# Board_A_Schematic.net
KiCad netlist of a schematic drawn in EasyEDA
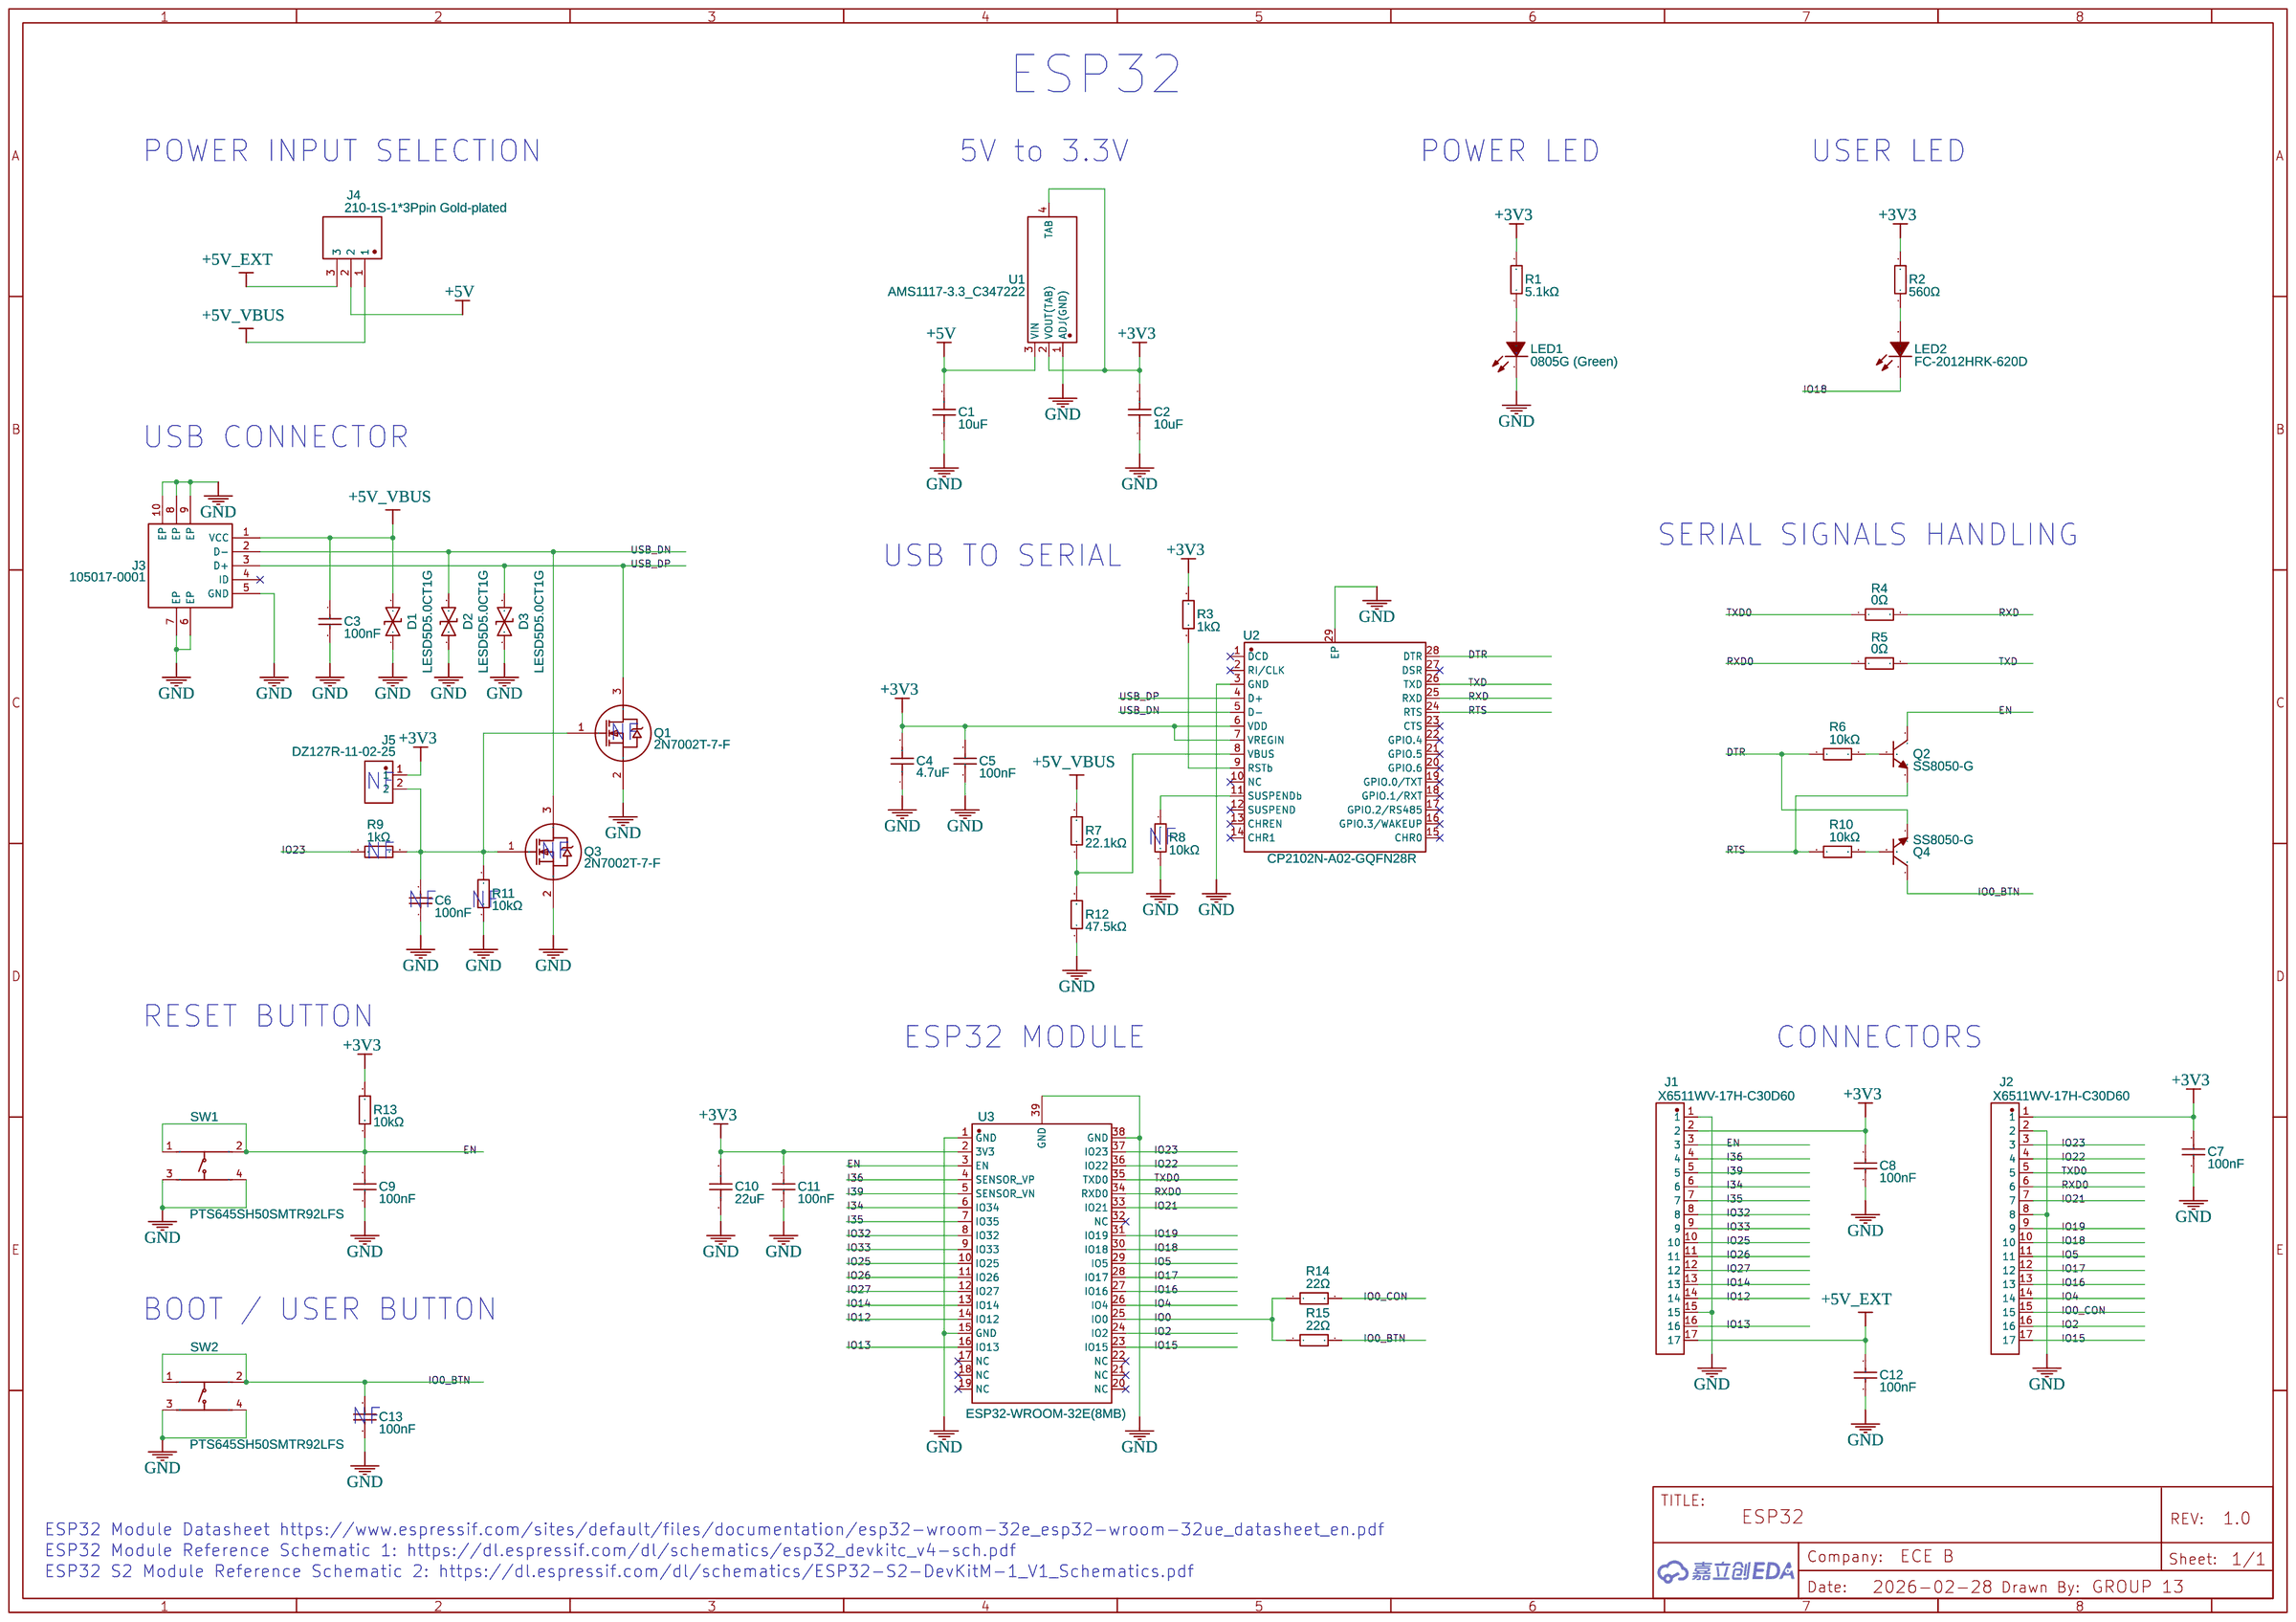
[diagram p0: schematic sheet]

(export (version "E")
  (design (tool "Eeschema 10.0.6"))
  (components
    (comp (ref "C1")
      (value "10uF")
      (fields
        (field (name "Manufacturer Part") "CL05A106MP5NUNC")
        (field (name "Manufacturer") "Samsung Electro-Mechanics")
      )
      (libsource (lib "") (part "CL05A106MP5NUNC_C315248"))
    )
    (comp (ref "C2")
      (value "10uF")
      (fields
        (field (name "Manufacturer Part") "CL05A106MP5NUNC")
        (field (name "Manufacturer") "Samsung Electro-Mechanics")
      )
      (libsource (lib "") (part "CL05A106MP5NUNC_C315248"))
    )
    (comp (ref "C3")
      (value "100nF")
      (fields (field (name "Manufacturer Part") "CL05B104KO5NNNC") (field (name "Manufacturer") "SAMSUNG"))
      (libsource (lib "") (part "CL05B104KO5NNNC"))
    )
    (comp (ref "C4")
      (value "4.7uF")
      (fields
        (field (name "Manufacturer Part") "CL05A475KP5NRNC")
        (field (name "Manufacturer") "Samsung Electro-Mechanics")
      )
      (libsource (lib "") (part "CL05A475KP5NRNC"))
    )
    (comp (ref "C5")
      (value "100nF")
      (fields (field (name "Manufacturer Part") "CL05B104KO5NNNC") (field (name "Manufacturer") "SAMSUNG"))
      (libsource (lib "") (part "CL05B104KO5NNNC"))
    )
    (comp (ref "C6")
      (value "100nF")
      (fields (field (name "Manufacturer Part") "CL05B104KO5NNNC") (field (name "Manufacturer") "SAMSUNG"))
      (libsource (lib "") (part "CL05B104KO5NNNC"))
    )
    (comp (ref "C7")
      (value "100nF")
      (fields (field (name "Manufacturer Part") "CL05B104KO5NNNC") (field (name "Manufacturer") "SAMSUNG"))
      (libsource (lib "") (part "CL05B104KO5NNNC"))
    )
    (comp (ref "C8")
      (value "100nF")
      (fields (field (name "Manufacturer Part") "CL05B104KO5NNNC") (field (name "Manufacturer") "SAMSUNG"))
      (libsource (lib "") (part "CL05B104KO5NNNC"))
    )
    (comp (ref "C9")
      (value "100nF")
      (fields (field (name "Manufacturer Part") "CL05B104KO5NNNC") (field (name "Manufacturer") "SAMSUNG"))
      (libsource (lib "") (part "CL05B104KO5NNNC"))
    )
    (comp (ref "C10")
      (value "22uF")
      (fields
        (field (name "Manufacturer Part") "CL21A226MAYNNNE")
        (field (name "Manufacturer") "Samsung Electro-Mechanics")
      )
      (libsource (lib "") (part "CL21A226MAYNNNE"))
    )
    (comp (ref "C11")
      (value "100nF")
      (fields (field (name "Manufacturer Part") "CL05B104KO5NNNC") (field (name "Manufacturer") "SAMSUNG"))
      (libsource (lib "") (part "CL05B104KO5NNNC"))
    )
    (comp (ref "C12")
      (value "100nF")
      (fields (field (name "Manufacturer Part") "CL05B104KO5NNNC") (field (name "Manufacturer") "SAMSUNG"))
      (libsource (lib "") (part "CL05B104KO5NNNC"))
    )
    (comp (ref "C13")
      (value "100nF")
      (fields (field (name "Manufacturer Part") "CL05B104KO5NNNC") (field (name "Manufacturer") "SAMSUNG"))
      (libsource (lib "") (part "CL05B104KO5NNNC"))
    )
    (comp (ref "D1")
      (value "LESD5D5.0CT1G")
      (fields (field (name "Manufacturer") "Leshan Radio"))
      (libsource (lib "") (part "LESD5D5.0CT1G"))
    )
    (comp (ref "D2")
      (value "LESD5D5.0CT1G")
      (fields (field (name "Manufacturer") "Leshan Radio"))
      (libsource (lib "") (part "LESD5D5.0CT1G"))
    )
    (comp (ref "D3")
      (value "LESD5D5.0CT1G")
      (fields (field (name "Manufacturer") "Leshan Radio"))
      (libsource (lib "") (part "LESD5D5.0CT1G"))
    )
    (comp (ref "J1")
      (value "X6511WV-17H-C30D60")
      (fields (field (name "Manufacturer") "XKB Connectivity"))
      (libsource (lib "") (part "X6511WV-17H-C30D60"))
    )
    (comp (ref "J2")
      (value "X6511WV-17H-C30D60")
      (fields (field (name "Manufacturer") "XKB Connectivity"))
      (libsource (lib "") (part "X6511WV-17H-C30D60"))
    )
    (comp (ref "J3")
      (value "105017-0001")
      (fields (field (name "Manufacturer") "MOLEX"))
      (libsource (lib "") (part "105017-0001"))
    )
    (comp (ref "J4")
      (value "210-1S-1*3Ppin Gold-plated")
      (fields (field (name "Manufacturer") "Ckmtw"))
      (libsource (lib "") (part "210-1S-1*3Ppin Gold-plated"))
    )
    (comp (ref "J5")
      (value "DZ127R-11-02-25")
      (fields (field (name "Manufacturer") "DEALON(德艺隆)"))
      (libsource (lib "") (part "DZ127R-11-02-25"))
    )
    (comp (ref "LED1")
      (value "0805G (Green)")
      (fields (field (name "Manufacturer") "KENTO"))
      (libsource (lib "") (part "0805G (Green)"))
    )
    (comp (ref "LED2")
      (value "FC-2012HRK-620D")
      (fields (field (name "Manufacturer") "NATIONSTAR"))
      (libsource (lib "") (part "FC-2012HRK-620D"))
    )
    (comp (ref "Q1")
      (value "2N7002T-7-F")
      (fields (field (name "Manufacturer") "DIODES"))
      (libsource (lib "") (part "2N7002T-7-F"))
    )
    (comp (ref "Q2")
      (value "SS8050-G")
      (fields (field (name "Manufacturer") "CJ(江苏长电/长晶)"))
      (libsource (lib "") (part "SS8050-G"))
    )
    (comp (ref "Q3")
      (value "2N7002T-7-F")
      (fields (field (name "Manufacturer") "DIODES"))
      (libsource (lib "") (part "2N7002T-7-F"))
    )
    (comp (ref "Q4")
      (value "SS8050-G")
      (fields (field (name "Manufacturer") "CJ(江苏长电/长晶)"))
      (libsource (lib "") (part "SS8050-G_1"))
    )
    (comp (ref "R1")
      (value "5.1kΩ")
      (fields (field (name "Manufacturer Part") "0402WGF5101TCE") (field (name "Manufacturer") "UniOhm"))
      (libsource (lib "") (part "0402WGF5101TCE"))
    )
    (comp (ref "R2")
      (value "560Ω")
      (fields (field (name "Manufacturer Part") "0402WGF5600TCE") (field (name "Manufacturer") "UniOhm"))
      (libsource (lib "") (part "0402WGF5600TCE"))
    )
    (comp (ref "R3")
      (value "1kΩ")
      (fields (field (name "Manufacturer Part") "0402WGF1001TCE") (field (name "Manufacturer") "UniOhm"))
      (libsource (lib "") (part "0402WGF1001TCE_1"))
    )
    (comp (ref "R4")
      (value "0Ω")
      (fields (field (name "Manufacturer Part") "0402WGF0000TCE") (field (name "Manufacturer") "UniOhm"))
      (libsource (lib "") (part "0402WGF0000TCE"))
    )
    (comp (ref "R5")
      (value "0Ω")
      (fields (field (name "Manufacturer Part") "0402WGF0000TCE") (field (name "Manufacturer") "UniOhm"))
      (libsource (lib "") (part "0402WGF0000TCE"))
    )
    (comp (ref "R6")
      (value "10kΩ")
      (fields (field (name "Manufacturer Part") "0402WGF1002TCE") (field (name "Manufacturer") "UniOhm"))
      (libsource (lib "") (part "0402WGF1002TCE_1"))
    )
    (comp (ref "R7")
      (value "22.1kΩ")
      (fields (field (name "Manufacturer Part") "0402WGF2212TCE") (field (name "Manufacturer") "UniOhm"))
      (libsource (lib "") (part "0402WGF2212TCE"))
    )
    (comp (ref "R8")
      (value "10kΩ")
      (fields (field (name "Manufacturer Part") "0402WGF1002TCE") (field (name "Manufacturer") "UniOhm"))
      (libsource (lib "") (part "0402WGF1002TCE"))
    )
    (comp (ref "R9")
      (value "1kΩ")
      (fields (field (name "Manufacturer Part") "0402WGF1001TCE") (field (name "Manufacturer") "UniOhm"))
      (libsource (lib "") (part "0402WGF1001TCE"))
    )
    (comp (ref "R10")
      (value "10kΩ")
      (fields (field (name "Manufacturer Part") "0402WGF1002TCE") (field (name "Manufacturer") "UniOhm"))
      (libsource (lib "") (part "0402WGF1002TCE_1"))
    )
    (comp (ref "R11")
      (value "10kΩ")
      (fields (field (name "Manufacturer Part") "0402WGF1002TCE") (field (name "Manufacturer") "UniOhm"))
      (libsource (lib "") (part "0402WGF1002TCE"))
    )
    (comp (ref "R12")
      (value "47.5kΩ")
      (fields (field (name "Manufacturer Part") "0402WGF4752TCE") (field (name "Manufacturer") "UniOhm"))
      (libsource (lib "") (part "0402WGF4752TCE"))
    )
    (comp (ref "R13")
      (value "10kΩ")
      (fields (field (name "Manufacturer Part") "0402WGF1002TCE") (field (name "Manufacturer") "UniOhm"))
      (libsource (lib "") (part "0402WGF1002TCE"))
    )
    (comp (ref "R14")
      (value "22Ω")
      (fields (field (name "Manufacturer Part") "0402WGF220JTCE") (field (name "Manufacturer") "UniOhm"))
      (libsource (lib "") (part "0402WGF220JTCE"))
    )
    (comp (ref "R15")
      (value "22Ω")
      (fields (field (name "Manufacturer Part") "0402WGF220JTCE") (field (name "Manufacturer") "UniOhm"))
      (libsource (lib "") (part "0402WGF220JTCE"))
    )
    (comp (ref "SW1")
      (value "PTS645SH50SMTR92LFS")
      (fields (field (name "Manufacturer") "C&K"))
      (libsource (lib "") (part "PTS645SH50SMTR92LFS"))
    )
    (comp (ref "SW2")
      (value "PTS645SH50SMTR92LFS")
      (fields (field (name "Manufacturer") "C&K"))
      (libsource (lib "") (part "PTS645SH50SMTR92LFS"))
    )
    (comp (ref "U1")
      (value "AMS1117-3.3_C347222")
      (fields
        (field (name "Manufacturer Part") "AMS1117-3.3")
        (field (name "Manufacturer") "Youtai Semiconductor Co., Ltd.")
      )
      (libsource (lib "") (part "AMS1117-3.3_C347222"))
    )
    (comp (ref "U2")
      (value "CP2102N-A02-GQFN28R")
      (fields (field (name "Manufacturer") "SILICON LABS(芯科)"))
      (libsource (lib "") (part "CP2102N-A02-GQFN28R"))
    )
    (comp (ref "U3")
      (value "ESP32-WROOM-32E(8MB)")
      (fields (field (name "Manufacturer") "Espressif Systems"))
      (libsource (lib "") (part "ESP32-WROOM-32E(8MB)"))
    )
  )
  (nets
    (net (code "1") (name "+3V3") (class "Default")
      (node (ref "C10") (pin "2") (pinfunction "2_2") (pintype "unspecified"))
      (node (ref "C11") (pin "2") (pinfunction "2_2") (pintype "input"))
      (node (ref "C2") (pin "2") (pinfunction "2_2") (pintype "unspecified"))
      (node (ref "C4") (pin "2") (pinfunction "2_2") (pintype "unspecified"))
      (node (ref "C5") (pin "2") (pinfunction "2_2") (pintype "input"))
      (node (ref "C7") (pin "2") (pinfunction "2_2") (pintype "input"))
      (node (ref "C8") (pin "2") (pinfunction "2_2") (pintype "input"))
      (node (ref "J1") (pin "2") (pinfunction "2_2") (pintype "unspecified"))
      (node (ref "J2") (pin "1") (pinfunction "1_1") (pintype "unspecified"))
      (node (ref "J5") (pin "1") (pinfunction "1_1") (pintype "unspecified"))
      (node (ref "R1") (pin "2") (pinfunction "2_2") (pintype "input"))
      (node (ref "R13") (pin "2") (pinfunction "2_2") (pintype "input"))
      (node (ref "R2") (pin "2") (pinfunction "2_2") (pintype "input"))
      (node (ref "R3") (pin "2") (pinfunction "2_2") (pintype "input"))
      (node (ref "U1") (pin "2") (pinfunction "VOUT(TAB)_2") (pintype "unspecified"))
      (node (ref "U1") (pin "4") (pinfunction "TAB_4") (pintype "unspecified"))
      (node (ref "U2") (pin "6") (pinfunction "VDD_6") (pintype "unspecified"))
      (node (ref "U2") (pin "7") (pinfunction "VREGIN_7") (pintype "unspecified"))
      (node (ref "U3") (pin "2") (pinfunction "3V3_2") (pintype "unspecified"))
    )
    (net (code "2") (name "+5V") (class "Default")
      (node (ref "C1") (pin "2") (pinfunction "2_2") (pintype "unspecified"))
      (node (ref "J4") (pin "2") (pinfunction "2_2") (pintype "unspecified"))
      (node (ref "U1") (pin "3") (pinfunction "VIN_3") (pintype "unspecified"))
    )
    (net (code "3") (name "+5V_EXT") (class "Default")
      (node (ref "C12") (pin "2") (pinfunction "2_2") (pintype "input"))
      (node (ref "J1") (pin "17") (pinfunction "17_17") (pintype "unspecified"))
      (node (ref "J4") (pin "3") (pinfunction "3_3") (pintype "unspecified"))
    )
    (net (code "4") (name "+5V_VBUS") (class "Default")
      (node (ref "C3") (pin "2") (pinfunction "2_2") (pintype "input"))
      (node (ref "D1") (pin "2") (pinfunction "2_2") (pintype "unspecified"))
      (node (ref "J3") (pin "1") (pinfunction "VCC_1") (pintype "unspecified"))
      (node (ref "J4") (pin "1") (pinfunction "1_1") (pintype "unspecified"))
      (node (ref "R7") (pin "2") (pinfunction "2_2") (pintype "input"))
    )
    (net (code "5") (name "/DTR") (class "Default")
      (node (ref "Q4") (pin "2") (pinfunction "E_2") (pintype "input"))
      (node (ref "R6") (pin "1") (pinfunction "1_1") (pintype "input"))
      (node (ref "U2") (pin "28") (pinfunction "DTR_28") (pintype "unspecified"))
    )
    (net (code "6") (name "/EN") (class "Default")
      (node (ref "C9") (pin "2") (pinfunction "2_2") (pintype "input"))
      (node (ref "J1") (pin "3") (pinfunction "3_3") (pintype "unspecified"))
      (node (ref "Q2") (pin "3") (pinfunction "C_3") (pintype "input"))
      (node (ref "R13") (pin "1") (pinfunction "1_1") (pintype "input"))
      (node (ref "SW1") (pin "1") (pinfunction "1_1") (pintype "unspecified"))
      (node (ref "SW1") (pin "2") (pinfunction "2_2") (pintype "unspecified"))
      (node (ref "U3") (pin "3") (pinfunction "EN_3") (pintype "unspecified"))
    )
    (net (code "7") (name "/I34") (class "Default")
      (node (ref "J1") (pin "6") (pinfunction "6_6") (pintype "unspecified"))
      (node (ref "U3") (pin "6") (pinfunction "IO34_6") (pintype "unspecified"))
    )
    (net (code "8") (name "/I35") (class "Default")
      (node (ref "J1") (pin "7") (pinfunction "7_7") (pintype "unspecified"))
      (node (ref "U3") (pin "7") (pinfunction "IO35_7") (pintype "unspecified"))
    )
    (net (code "9") (name "/I36") (class "Default")
      (node (ref "J1") (pin "4") (pinfunction "4_4") (pintype "unspecified"))
      (node (ref "U3") (pin "4") (pinfunction "SENSOR_VP_4") (pintype "unspecified"))
    )
    (net (code "10") (name "/I39") (class "Default")
      (node (ref "J1") (pin "5") (pinfunction "5_5") (pintype "unspecified"))
      (node (ref "U3") (pin "5") (pinfunction "SENSOR_VN_5") (pintype "unspecified"))
    )
    (net (code "11") (name "/IO0") (class "Default")
      (node (ref "R14") (pin "1") (pinfunction "1_1") (pintype "input"))
      (node (ref "R15") (pin "1") (pinfunction "1_1") (pintype "input"))
      (node (ref "U3") (pin "25") (pinfunction "IO0_25") (pintype "unspecified"))
    )
    (net (code "12") (name "/IO0_BTN") (class "Default")
      (node (ref "C13") (pin "2") (pinfunction "2_2") (pintype "input"))
      (node (ref "Q4") (pin "3") (pinfunction "C_3") (pintype "input"))
      (node (ref "R15") (pin "2") (pinfunction "2_2") (pintype "input"))
      (node (ref "SW2") (pin "1") (pinfunction "1_1") (pintype "unspecified"))
      (node (ref "SW2") (pin "2") (pinfunction "2_2") (pintype "unspecified"))
    )
    (net (code "13") (name "/IO0_CON") (class "Default")
      (node (ref "J2") (pin "15") (pinfunction "15_15") (pintype "unspecified"))
      (node (ref "R14") (pin "2") (pinfunction "2_2") (pintype "input"))
    )
    (net (code "14") (name "/IO2") (class "Default")
      (node (ref "J2") (pin "16") (pinfunction "16_16") (pintype "unspecified"))
      (node (ref "U3") (pin "24") (pinfunction "IO2_24") (pintype "unspecified"))
    )
    (net (code "15") (name "/IO4") (class "Default")
      (node (ref "J2") (pin "14") (pinfunction "14_14") (pintype "unspecified"))
      (node (ref "U3") (pin "26") (pinfunction "IO4_26") (pintype "unspecified"))
    )
    (net (code "16") (name "/IO5") (class "Default")
      (node (ref "J2") (pin "11") (pinfunction "11_11") (pintype "unspecified"))
      (node (ref "U3") (pin "29") (pinfunction "IO5_29") (pintype "unspecified"))
    )
    (net (code "17") (name "/IO12") (class "Default")
      (node (ref "J1") (pin "14") (pinfunction "14_14") (pintype "unspecified"))
      (node (ref "U3") (pin "14") (pinfunction "IO12_14") (pintype "unspecified"))
    )
    (net (code "18") (name "/IO13") (class "Default")
      (node (ref "J1") (pin "16") (pinfunction "16_16") (pintype "unspecified"))
      (node (ref "U3") (pin "16") (pinfunction "IO13_16") (pintype "unspecified"))
    )
    (net (code "19") (name "/IO14") (class "Default")
      (node (ref "J1") (pin "13") (pinfunction "13_13") (pintype "unspecified"))
      (node (ref "U3") (pin "13") (pinfunction "IO14_13") (pintype "unspecified"))
    )
    (net (code "20") (name "/IO15") (class "Default")
      (node (ref "J2") (pin "17") (pinfunction "17_17") (pintype "unspecified"))
      (node (ref "U3") (pin "23") (pinfunction "IO15_23") (pintype "unspecified"))
    )
    (net (code "21") (name "/IO16") (class "Default")
      (node (ref "J2") (pin "13") (pinfunction "13_13") (pintype "unspecified"))
      (node (ref "U3") (pin "27") (pinfunction "IO16_27") (pintype "unspecified"))
    )
    (net (code "22") (name "/IO17") (class "Default")
      (node (ref "J2") (pin "12") (pinfunction "12_12") (pintype "unspecified"))
      (node (ref "U3") (pin "28") (pinfunction "IO17_28") (pintype "unspecified"))
    )
    (net (code "23") (name "/IO18") (class "Default")
      (node (ref "J2") (pin "10") (pinfunction "10_10") (pintype "unspecified"))
      (node (ref "LED2") (pin "1") (pinfunction "-_1") (pintype "unspecified"))
      (node (ref "U3") (pin "30") (pinfunction "IO18_30") (pintype "unspecified"))
    )
    (net (code "24") (name "/IO19") (class "Default")
      (node (ref "J2") (pin "9") (pinfunction "9_9") (pintype "unspecified"))
      (node (ref "U3") (pin "31") (pinfunction "IO19_31") (pintype "unspecified"))
    )
    (net (code "25") (name "/IO21") (class "Default")
      (node (ref "J2") (pin "7") (pinfunction "7_7") (pintype "unspecified"))
      (node (ref "U3") (pin "33") (pinfunction "IO21_33") (pintype "unspecified"))
    )
    (net (code "26") (name "/IO22") (class "Default")
      (node (ref "J2") (pin "4") (pinfunction "4_4") (pintype "unspecified"))
      (node (ref "U3") (pin "36") (pinfunction "IO22_36") (pintype "unspecified"))
    )
    (net (code "27") (name "/IO23") (class "Default")
      (node (ref "J2") (pin "3") (pinfunction "3_3") (pintype "unspecified"))
      (node (ref "R9") (pin "2") (pinfunction "2_2") (pintype "input"))
      (node (ref "U3") (pin "37") (pinfunction "IO23_37") (pintype "unspecified"))
    )
    (net (code "28") (name "/IO25") (class "Default")
      (node (ref "J1") (pin "10") (pinfunction "10_10") (pintype "unspecified"))
      (node (ref "U3") (pin "10") (pinfunction "IO25_10") (pintype "unspecified"))
    )
    (net (code "29") (name "/IO26") (class "Default")
      (node (ref "J1") (pin "11") (pinfunction "11_11") (pintype "unspecified"))
      (node (ref "U3") (pin "11") (pinfunction "IO26_11") (pintype "unspecified"))
    )
    (net (code "30") (name "/IO27") (class "Default")
      (node (ref "J1") (pin "12") (pinfunction "12_12") (pintype "unspecified"))
      (node (ref "U3") (pin "12") (pinfunction "IO27_12") (pintype "unspecified"))
    )
    (net (code "31") (name "/IO32") (class "Default")
      (node (ref "J1") (pin "8") (pinfunction "8_8") (pintype "unspecified"))
      (node (ref "U3") (pin "8") (pinfunction "IO32_8") (pintype "unspecified"))
    )
    (net (code "32") (name "/IO33") (class "Default")
      (node (ref "J1") (pin "9") (pinfunction "9_9") (pintype "unspecified"))
      (node (ref "U3") (pin "9") (pinfunction "IO33_9") (pintype "unspecified"))
    )
    (net (code "33") (name "/RTS") (class "Default")
      (node (ref "Q2") (pin "2") (pinfunction "E_2") (pintype "input"))
      (node (ref "R10") (pin "1") (pinfunction "1_1") (pintype "input"))
      (node (ref "U2") (pin "24") (pinfunction "RTS_24") (pintype "unspecified"))
    )
    (net (code "34") (name "/RXD") (class "Default")
      (node (ref "R4") (pin "2") (pinfunction "2_2") (pintype "input"))
      (node (ref "U2") (pin "25") (pinfunction "RXD_25") (pintype "unspecified"))
    )
    (net (code "35") (name "/RXD0") (class "Default")
      (node (ref "J2") (pin "6") (pinfunction "6_6") (pintype "unspecified"))
      (node (ref "R5") (pin "1") (pinfunction "1_1") (pintype "input"))
      (node (ref "U3") (pin "34") (pinfunction "RXD0_34") (pintype "unspecified"))
    )
    (net (code "36") (name "/TXD") (class "Default")
      (node (ref "R5") (pin "2") (pinfunction "2_2") (pintype "input"))
      (node (ref "U2") (pin "26") (pinfunction "TXD_26") (pintype "unspecified"))
    )
    (net (code "37") (name "/TXD0") (class "Default")
      (node (ref "J2") (pin "5") (pinfunction "5_5") (pintype "unspecified"))
      (node (ref "R4") (pin "1") (pinfunction "1_1") (pintype "input"))
      (node (ref "U3") (pin "35") (pinfunction "TXD0_35") (pintype "unspecified"))
    )
    (net (code "38") (name "/USB_DN") (class "Default")
      (node (ref "D2") (pin "2") (pinfunction "2_2") (pintype "unspecified"))
      (node (ref "J3") (pin "2") (pinfunction "D-_2") (pintype "unspecified"))
      (node (ref "Q3") (pin "3") (pinfunction "D_3") (pintype "unspecified"))
      (node (ref "U2") (pin "5") (pinfunction "D-_5") (pintype "unspecified"))
    )
    (net (code "39") (name "/USB_DP") (class "Default")
      (node (ref "D3") (pin "2") (pinfunction "2_2") (pintype "unspecified"))
      (node (ref "J3") (pin "3") (pinfunction "D+_3") (pintype "unspecified"))
      (node (ref "Q1") (pin "3") (pinfunction "D_3") (pintype "unspecified"))
      (node (ref "U2") (pin "4") (pinfunction "D+_4") (pintype "unspecified"))
    )
    (net (code "40") (name "GND") (class "Default")
      (node (ref "C1") (pin "1") (pinfunction "1_1") (pintype "unspecified"))
      (node (ref "C10") (pin "1") (pinfunction "1_1") (pintype "unspecified"))
      (node (ref "C11") (pin "1") (pinfunction "1_1") (pintype "input"))
      (node (ref "C12") (pin "1") (pinfunction "1_1") (pintype "input"))
      (node (ref "C13") (pin "1") (pinfunction "1_1") (pintype "input"))
      (node (ref "C2") (pin "1") (pinfunction "1_1") (pintype "unspecified"))
      (node (ref "C3") (pin "1") (pinfunction "1_1") (pintype "input"))
      (node (ref "C4") (pin "1") (pinfunction "1_1") (pintype "unspecified"))
      (node (ref "C5") (pin "1") (pinfunction "1_1") (pintype "input"))
      (node (ref "C6") (pin "1") (pinfunction "1_1") (pintype "input"))
      (node (ref "C7") (pin "1") (pinfunction "1_1") (pintype "input"))
      (node (ref "C8") (pin "1") (pinfunction "1_1") (pintype "input"))
      (node (ref "C9") (pin "1") (pinfunction "1_1") (pintype "input"))
      (node (ref "D1") (pin "1") (pinfunction "1_1") (pintype "unspecified"))
      (node (ref "D2") (pin "1") (pinfunction "1_1") (pintype "unspecified"))
      (node (ref "D3") (pin "1") (pinfunction "1_1") (pintype "unspecified"))
      (node (ref "J1") (pin "1") (pinfunction "1_1") (pintype "unspecified"))
      (node (ref "J1") (pin "15") (pinfunction "15_15") (pintype "unspecified"))
      (node (ref "J2") (pin "2") (pinfunction "2_2") (pintype "unspecified"))
      (node (ref "J2") (pin "8") (pinfunction "8_8") (pintype "unspecified"))
      (node (ref "J3") (pin "10") (pinfunction "EP_10") (pintype "unspecified"))
      (node (ref "J3") (pin "5") (pinfunction "GND_5") (pintype "unspecified"))
      (node (ref "J3") (pin "6") (pinfunction "EP_6") (pintype "unspecified"))
      (node (ref "J3") (pin "7") (pinfunction "EP_7") (pintype "unspecified"))
      (node (ref "J3") (pin "8") (pinfunction "EP_8") (pintype "unspecified"))
      (node (ref "J3") (pin "9") (pinfunction "EP_9") (pintype "unspecified"))
      (node (ref "LED1") (pin "1") (pinfunction "K_1") (pintype "unspecified"))
      (node (ref "Q1") (pin "2") (pinfunction "S_2") (pintype "unspecified"))
      (node (ref "Q3") (pin "2") (pinfunction "S_2") (pintype "unspecified"))
      (node (ref "R11") (pin "1") (pinfunction "1_1") (pintype "input"))
      (node (ref "R12") (pin "1") (pinfunction "1_1") (pintype "input"))
      (node (ref "R8") (pin "1") (pinfunction "1_1") (pintype "input"))
      (node (ref "SW1") (pin "3") (pinfunction "3_3") (pintype "unspecified"))
      (node (ref "SW1") (pin "4") (pinfunction "4_4") (pintype "unspecified"))
      (node (ref "SW2") (pin "3") (pinfunction "3_3") (pintype "unspecified"))
      (node (ref "SW2") (pin "4") (pinfunction "4_4") (pintype "unspecified"))
      (node (ref "U1") (pin "1") (pinfunction "ADJ(GND)_1") (pintype "unspecified"))
      (node (ref "U2") (pin "29") (pinfunction "EP_29") (pintype "unspecified"))
      (node (ref "U2") (pin "3") (pinfunction "GND_3") (pintype "unspecified"))
      (node (ref "U3") (pin "1") (pinfunction "GND_1") (pintype "unspecified"))
      (node (ref "U3") (pin "15") (pinfunction "GND_15") (pintype "unspecified"))
      (node (ref "U3") (pin "38") (pinfunction "GND_38") (pintype "unspecified"))
      (node (ref "U3") (pin "39") (pinfunction "GND_39") (pintype "unspecified"))
    )
    (net (code "41") (name "Net-(LED1-A)") (class "Default")
      (node (ref "LED1") (pin "2") (pinfunction "A_2") (pintype "unspecified"))
      (node (ref "R1") (pin "1") (pinfunction "1_1") (pintype "input"))
    )
    (net (code "42") (name "Net-(LED2-+)") (class "Default")
      (node (ref "LED2") (pin "2") (pinfunction "+_2") (pintype "unspecified"))
      (node (ref "R2") (pin "1") (pinfunction "1_1") (pintype "input"))
    )
    (net (code "43") (name "Net-(Q1-G)") (class "Default")
      (node (ref "C6") (pin "2") (pinfunction "2_2") (pintype "input"))
      (node (ref "J5") (pin "2") (pinfunction "2_2") (pintype "unspecified"))
      (node (ref "Q1") (pin "1") (pinfunction "G_1") (pintype "unspecified"))
      (node (ref "Q3") (pin "1") (pinfunction "G_1") (pintype "unspecified"))
      (node (ref "R11") (pin "2") (pinfunction "2_2") (pintype "input"))
      (node (ref "R9") (pin "1") (pinfunction "1_1") (pintype "input"))
    )
    (net (code "44") (name "Net-(Q2-B)") (class "Default")
      (node (ref "Q2") (pin "1") (pinfunction "B_1") (pintype "input"))
      (node (ref "R6") (pin "2") (pinfunction "2_2") (pintype "input"))
    )
    (net (code "45") (name "Net-(Q4-B)") (class "Default")
      (node (ref "Q4") (pin "1") (pinfunction "B_1") (pintype "input"))
      (node (ref "R10") (pin "2") (pinfunction "2_2") (pintype "input"))
    )
    (net (code "46") (name "Net-(U2-RSTb)") (class "Default")
      (node (ref "R3") (pin "1") (pinfunction "1_1") (pintype "input"))
      (node (ref "U2") (pin "9") (pinfunction "RSTb_9") (pintype "unspecified"))
    )
    (net (code "47") (name "Net-(U2-SUSPENDb)") (class "Default")
      (node (ref "R8") (pin "2") (pinfunction "2_2") (pintype "input"))
      (node (ref "U2") (pin "11") (pinfunction "SUSPENDb_11") (pintype "unspecified"))
    )
    (net (code "48") (name "Net-(U2-VBUS)") (class "Default")
      (node (ref "R12") (pin "2") (pinfunction "2_2") (pintype "input"))
      (node (ref "R7") (pin "1") (pinfunction "1_1") (pintype "input"))
      (node (ref "U2") (pin "8") (pinfunction "VBUS_8") (pintype "unspecified"))
    )
    (net (code "49") (name "unconnected-(J3-ID-Pad4)") (class "Default")
      (node (ref "J3") (pin "4") (pinfunction "ID_4") (pintype "unspecified+no_connect"))
    )
    (net (code "50") (name "unconnected-(U2-CHR0-Pad15)") (class "Default")
      (node (ref "U2") (pin "15") (pinfunction "CHR0_15") (pintype "unspecified+no_connect"))
    )
    (net (code "51") (name "unconnected-(U2-CHR1-Pad14)") (class "Default")
      (node (ref "U2") (pin "14") (pinfunction "CHR1_14") (pintype "unspecified+no_connect"))
    )
    (net (code "52") (name "unconnected-(U2-CHREN-Pad13)") (class "Default")
      (node (ref "U2") (pin "13") (pinfunction "CHREN_13") (pintype "unspecified+no_connect"))
    )
    (net (code "53") (name "unconnected-(U2-CTS-Pad23)") (class "Default")
      (node (ref "U2") (pin "23") (pinfunction "CTS_23") (pintype "unspecified+no_connect"))
    )
    (net (code "54") (name "unconnected-(U2-DCD-Pad1)") (class "Default")
      (node (ref "U2") (pin "1") (pinfunction "DCD_1") (pintype "unspecified+no_connect"))
    )
    (net (code "55") (name "unconnected-(U2-DSR-Pad27)") (class "Default")
      (node (ref "U2") (pin "27") (pinfunction "DSR_27") (pintype "unspecified+no_connect"))
    )
    (net (code "56") (name "unconnected-(U2-GPIO.0{slash}TXT-Pad19)") (class "Default")
      (node (ref "U2") (pin "19") (pinfunction "GPIO.0/TXT_19") (pintype "unspecified+no_connect"))
    )
    (net (code "57") (name "unconnected-(U2-GPIO.1{slash}RXT-Pad18)") (class "Default")
      (node (ref "U2") (pin "18") (pinfunction "GPIO.1/RXT_18") (pintype "unspecified+no_connect"))
    )
    (net (code "58") (name "unconnected-(U2-GPIO.2{slash}RS485-Pad17)") (class "Default")
      (node (ref "U2") (pin "17") (pinfunction "GPIO.2/RS485_17") (pintype "unspecified+no_connect"))
    )
    (net (code "59") (name "unconnected-(U2-GPIO.3{slash}WAKEUP-Pad16)") (class "Default")
      (node (ref "U2") (pin "16") (pinfunction "GPIO.3/WAKEUP_16") (pintype "unspecified+no_connect"))
    )
    (net (code "60") (name "unconnected-(U2-GPIO.4-Pad22)") (class "Default")
      (node (ref "U2") (pin "22") (pinfunction "GPIO.4_22") (pintype "unspecified+no_connect"))
    )
    (net (code "61") (name "unconnected-(U2-GPIO.5-Pad21)") (class "Default")
      (node (ref "U2") (pin "21") (pinfunction "GPIO.5_21") (pintype "unspecified+no_connect"))
    )
    (net (code "62") (name "unconnected-(U2-GPIO.6-Pad20)") (class "Default")
      (node (ref "U2") (pin "20") (pinfunction "GPIO.6_20") (pintype "unspecified+no_connect"))
    )
    (net (code "63") (name "unconnected-(U2-NC-Pad10)") (class "Default")
      (node (ref "U2") (pin "10") (pinfunction "NC_10") (pintype "unspecified+no_connect"))
    )
    (net (code "64") (name "unconnected-(U2-RI{slash}CLK-Pad2)") (class "Default")
      (node (ref "U2") (pin "2") (pinfunction "RI/CLK_2") (pintype "unspecified+no_connect"))
    )
    (net (code "65") (name "unconnected-(U2-SUSPEND-Pad12)") (class "Default")
      (node (ref "U2") (pin "12") (pinfunction "SUSPEND_12") (pintype "unspecified+no_connect"))
    )
    (net (code "66") (name "unconnected-(U3-NC-Pad17)") (class "Default")
      (node (ref "U3") (pin "17") (pinfunction "NC_17") (pintype "unspecified+no_connect"))
    )
    (net (code "67") (name "unconnected-(U3-NC-Pad18)") (class "Default")
      (node (ref "U3") (pin "18") (pinfunction "NC_18") (pintype "unspecified+no_connect"))
    )
    (net (code "68") (name "unconnected-(U3-NC-Pad19)") (class "Default")
      (node (ref "U3") (pin "19") (pinfunction "NC_19") (pintype "unspecified+no_connect"))
    )
    (net (code "69") (name "unconnected-(U3-NC-Pad20)") (class "Default")
      (node (ref "U3") (pin "20") (pinfunction "NC_20") (pintype "unspecified+no_connect"))
    )
    (net (code "70") (name "unconnected-(U3-NC-Pad21)") (class "Default")
      (node (ref "U3") (pin "21") (pinfunction "NC_21") (pintype "unspecified+no_connect"))
    )
    (net (code "71") (name "unconnected-(U3-NC-Pad22)") (class "Default")
      (node (ref "U3") (pin "22") (pinfunction "NC_22") (pintype "unspecified+no_connect"))
    )
    (net (code "72") (name "unconnected-(U3-NC-Pad32)") (class "Default")
      (node (ref "U3") (pin "32") (pinfunction "NC_32") (pintype "unspecified+no_connect"))
    )
  )
)
